# Tastendruckverlaengerer_1_3a.net
KiCad netlist of a schematic drawn in EAGLE
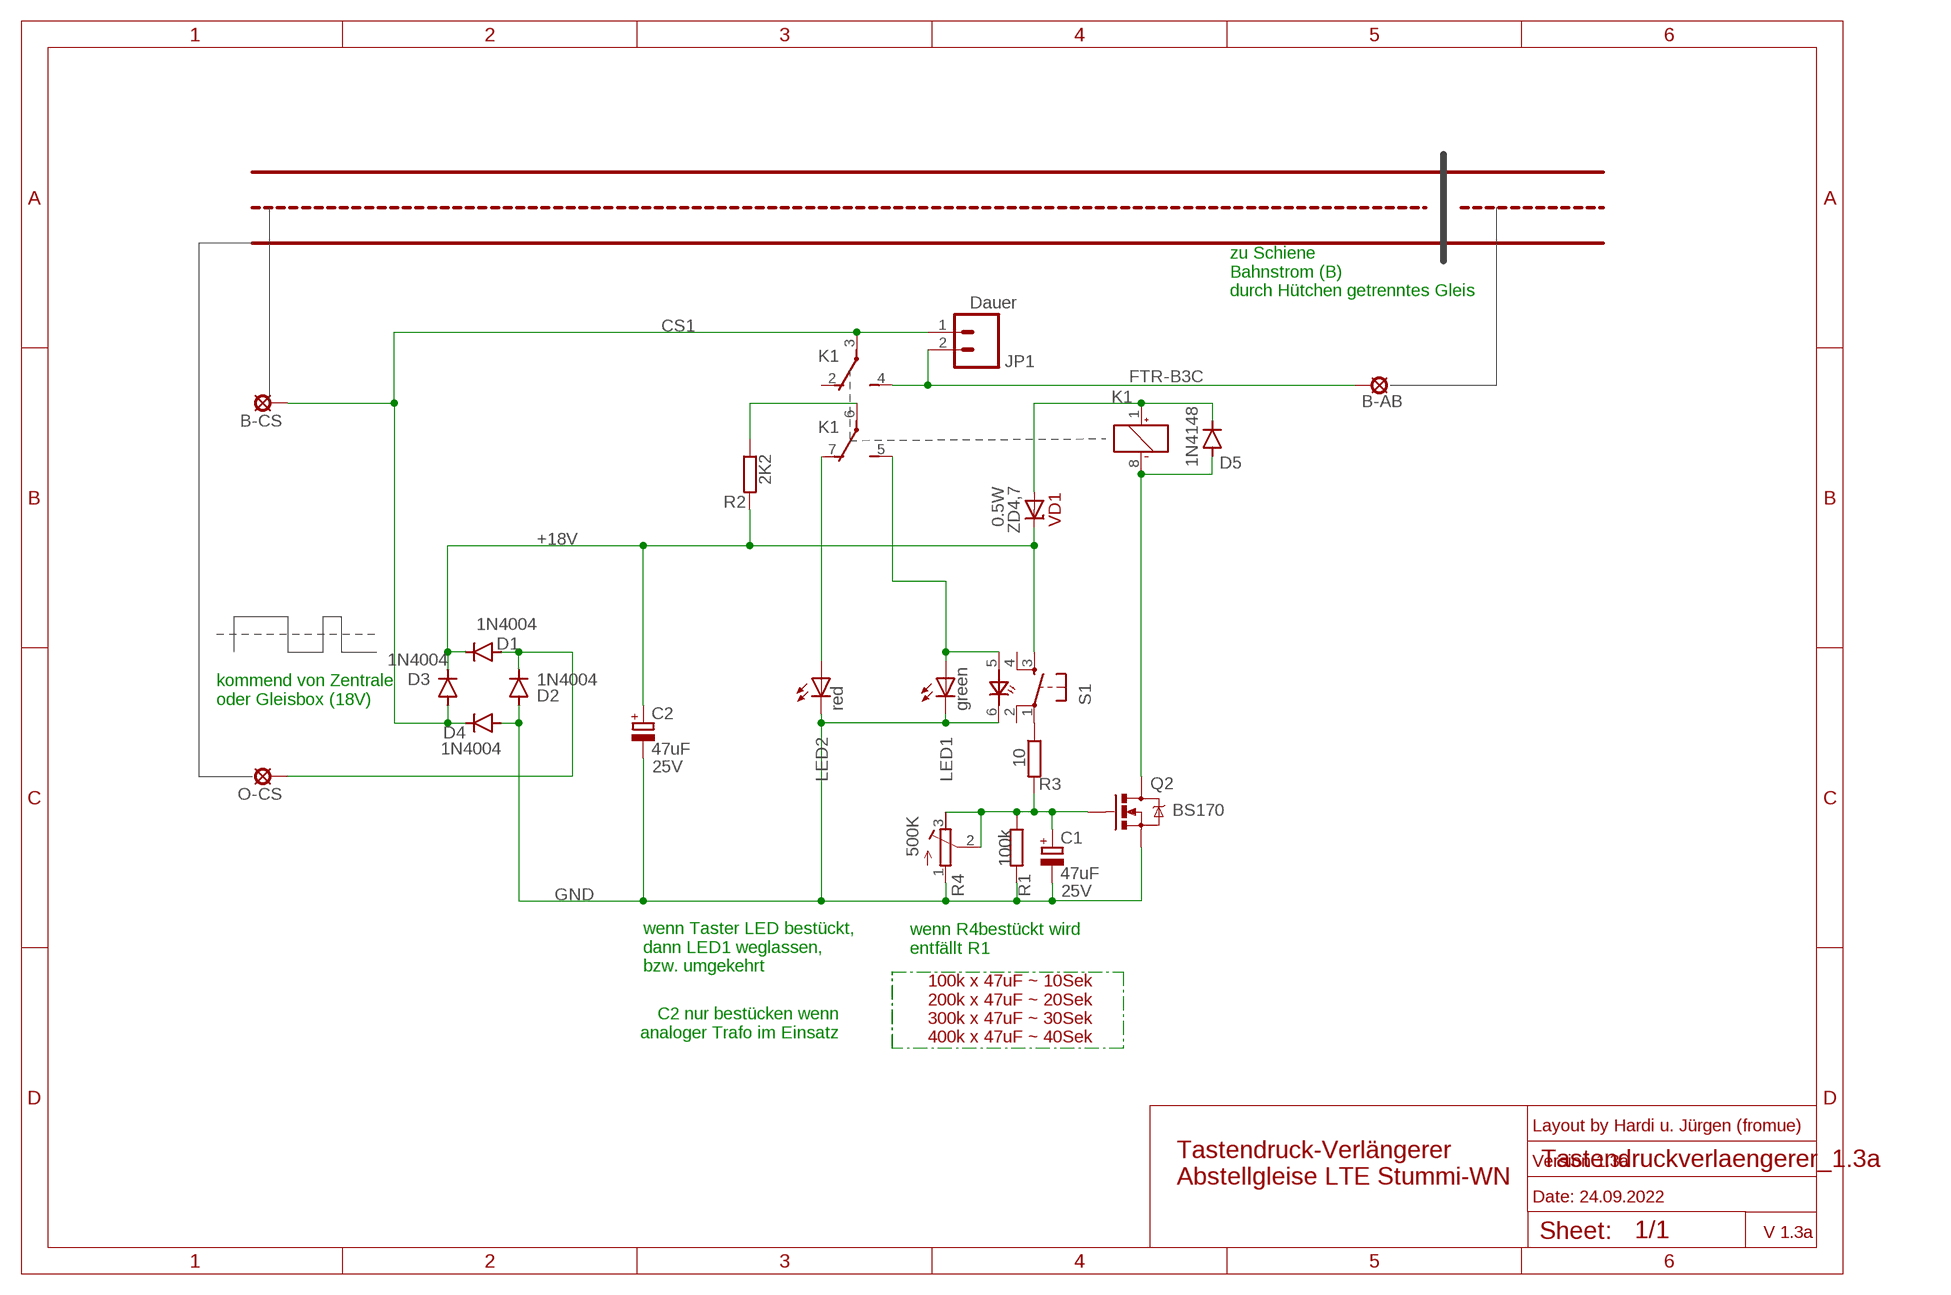
[diagram p0: schematic, sheet 1]

(export (version "E")
  (design (tool "Eeschema 10.0.6"))
  (components
    (comp (ref "B-AB")
      (value "SE14")
      (footprint "eagle-import:SE14")
      (libsource (lib "eagle-import") (part "SE14"))
    )
    (comp (ref "B-CS")
      (value "SE14")
      (footprint "eagle-import:SE14")
      (libsource (lib "eagle-import") (part "SE14"))
    )
    (comp (ref "C1")
      (value "47uF")
      (footprint "eagle-import:TT2D5L")
      (fields (field (name "ADD") "25V"))
      (libsource (lib "eagle-import") (part "CPOL-EUTT2D5L"))
    )
    (comp (ref "C2")
      (value "47uF")
      (footprint "eagle-import:TT2D5L")
      (fields (field (name "ADD") "25V"))
      (libsource (lib "eagle-import") (part "CPOL-EUTT2D5L"))
    )
    (comp (ref "D1")
      (value "1N4004")
      (footprint "eagle-import:DO41-10A")
      (libsource (lib "eagle-import") (part "1N4004DO41-10A"))
    )
    (comp (ref "D2")
      (value "1N4004")
      (footprint "eagle-import:DO41-10A")
      (libsource (lib "eagle-import") (part "1N4004DO41-10A"))
    )
    (comp (ref "D3")
      (value "1N4004")
      (footprint "eagle-import:DO41-10A")
      (libsource (lib "eagle-import") (part "1N4004DO41-10A"))
    )
    (comp (ref "D4")
      (value "1N4004")
      (footprint "eagle-import:DO41-10A")
      (libsource (lib "eagle-import") (part "1N4004DO41-10A"))
    )
    (comp (ref "D5")
      (value "1N4148")
      (footprint "eagle-import:DO35-7")
      (fields (field (name "SPICEPREFIX") "D"))
      (libsource (lib "eagle-import") (part "1N4148DO35-7"))
    )
    (comp (ref "JP1")
      (value "Dauer")
      (footprint "eagle-import:1X02")
      (libsource (lib "eagle-import") (part "M02PTH"))
    )
    (comp (ref "K1")
      (value "FTR-B3C")
      (footprint "eagle-import:FTR-B4C")
      (libsource (lib "eagle-import") (part "FTR-B3C"))
    )
    (comp (ref "LED1")
      (value "green")
      (footprint "eagle-import:LED3MM")
      (libsource (lib "eagle-import") (part "LED3MM"))
    )
    (comp (ref "LED2")
      (value "red")
      (footprint "eagle-import:LED3MM")
      (libsource (lib "eagle-import") (part "LED3MM"))
    )
    (comp (ref "O-CS")
      (value "SE14")
      (footprint "eagle-import:SE14")
      (libsource (lib "eagle-import") (part "SE14"))
    )
    (comp (ref "Q2")
      (value "BS170")
      (footprint "eagle-import:TO-92")
      (libsource (lib "eagle-import") (part "MOSFET-NCHANNELBS170"))
    )
    (comp (ref "R1")
      (value "100k")
      (footprint "eagle-import:0204_7")
      (libsource (lib "eagle-import") (part "R0204/7"))
    )
    (comp (ref "R2")
      (value "2K2")
      (footprint "eagle-import:0204_7")
      (fields (field (name "SPICEPREFIX") "4k7"))
      (libsource (lib "eagle-import") (part "R0204/7"))
    )
    (comp (ref "R3")
      (value "10")
      (footprint "eagle-import:0204_7")
      (libsource (lib "eagle-import") (part "R0204/7"))
    )
    (comp (ref "R4")
      (value "500K")
      (footprint "eagle-import:RTRIM3296W")
      (libsource (lib "eagle-import") (part "R-TRIMM3296W"))
    )
    (comp (ref "S1")
      (value "TASTER_LEDTC-1198-B")
      (footprint "eagle-import:TASTER_LED")
      (libsource (lib "eagle-import") (part "TASTER_LEDTC-1198-B"))
    )
    (comp (ref "VD1")
      (value "ZD4,7")
      (footprint "eagle-import:DIODES-ZENER_DO35-7")
      (fields (field (name "MOUSER") "ZF4.7") (field (name "POWER") "0.5W"))
      (libsource (lib "eagle-import") (part "DIODES-ZENER_?5.6V(1N5232)"))
    )
  )
  (nets
    (net (code "1") (name "/+18V") (class "Default")
      (node (ref "C2") (pin "+") (pinfunction "+_+") (pintype "passive"))
      (node (ref "D1") (pin "C") (pinfunction "C_C") (pintype "passive"))
      (node (ref "D3") (pin "C") (pinfunction "C_C") (pintype "passive"))
      (node (ref "R2") (pin "2") (pinfunction "2_2") (pintype "passive"))
      (node (ref "S1") (pin "3") (pinfunction "S_3") (pintype "passive"))
      (node (ref "VD1") (pin "C") (pinfunction "C_C") (pintype "passive"))
    )
    (net (code "2") (name "/CS1") (class "Default")
      (node (ref "B-CS") (pin "MP") (pinfunction "MP_MP") (pintype "passive"))
      (node (ref "D3") (pin "A") (pinfunction "A_A") (pintype "passive"))
      (node (ref "D4") (pin "C") (pinfunction "C_C") (pintype "passive"))
      (node (ref "JP1") (pin "1") (pinfunction "1_1") (pintype "passive"))
      (node (ref "K1") (pin "3") (pinfunction "P_3") (pintype "passive"))
    )
    (net (code "3") (name "/GND") (class "Default")
      (node (ref "C1") (pin "-") (pinfunction "-_-") (pintype "passive"))
      (node (ref "C2") (pin "-") (pinfunction "-_-") (pintype "passive"))
      (node (ref "D2") (pin "A") (pinfunction "A_A") (pintype "passive"))
      (node (ref "D4") (pin "A") (pinfunction "A_A") (pintype "passive"))
      (node (ref "LED1") (pin "K") (pinfunction "C_K") (pintype "passive"))
      (node (ref "LED2") (pin "K") (pinfunction "C_K") (pintype "passive"))
      (node (ref "Q2") (pin "3") (pinfunction "S_3") (pintype "passive"))
      (node (ref "R1") (pin "2") (pinfunction "2_2") (pintype "passive"))
      (node (ref "R4") (pin "1") (pinfunction "A_1") (pintype "passive"))
      (node (ref "S1") (pin "6") (pinfunction "-_6") (pintype "input"))
    )
    (net (code "4") (name "Net-(D1-PadA)") (class "Default")
      (node (ref "D1") (pin "A") (pinfunction "A_A") (pintype "passive"))
      (node (ref "D2") (pin "C") (pinfunction "C_C") (pintype "passive"))
      (node (ref "O-CS") (pin "MP") (pinfunction "MP_MP") (pintype "passive"))
    )
    (net (code "5") (name "Net-(K1A-S)") (class "Default")
      (node (ref "B-AB") (pin "MP") (pinfunction "MP_MP") (pintype "passive"))
      (node (ref "JP1") (pin "2") (pinfunction "2_2") (pintype "passive"))
      (node (ref "K1") (pin "4") (pinfunction "S_4") (pintype "passive"))
    )
    (net (code "6") (name "Net-(K1B-O)") (class "Default")
      (node (ref "K1") (pin "7") (pinfunction "O_7") (pintype "passive"))
      (node (ref "LED2") (pin "A") (pinfunction "A_A") (pintype "passive"))
    )
    (net (code "7") (name "Net-(K1B-P)") (class "Default")
      (node (ref "K1") (pin "6") (pinfunction "P_6") (pintype "passive"))
      (node (ref "R2") (pin "1") (pinfunction "1_1") (pintype "passive"))
    )
    (net (code "8") (name "Net-(K1B-S)") (class "Default")
      (node (ref "K1") (pin "5") (pinfunction "S_5") (pintype "passive"))
      (node (ref "LED1") (pin "A") (pinfunction "A_A") (pintype "passive"))
      (node (ref "S1") (pin "5") (pinfunction "+_5") (pintype "input"))
    )
    (net (code "9") (name "Net-(K1C-+)") (class "Default")
      (node (ref "D5") (pin "C") (pinfunction "C_C") (pintype "passive"))
      (node (ref "K1") (pin "1") (pinfunction "+_1") (pintype "passive"))
      (node (ref "VD1") (pin "A") (pinfunction "A_A") (pintype "passive"))
    )
    (net (code "10") (name "Net-(K1C--)") (class "Default")
      (node (ref "D5") (pin "A") (pinfunction "A_A") (pintype "passive"))
      (node (ref "K1") (pin "8") (pinfunction "-_8") (pintype "passive"))
      (node (ref "Q2") (pin "1") (pinfunction "D_1") (pintype "passive"))
    )
    (net (code "11") (name "Net-(Q2-G)") (class "Default")
      (node (ref "C1") (pin "+") (pinfunction "+_+") (pintype "passive"))
      (node (ref "Q2") (pin "2") (pinfunction "G_2") (pintype "passive"))
      (node (ref "R1") (pin "1") (pinfunction "1_1") (pintype "passive"))
      (node (ref "R3") (pin "2") (pinfunction "2_2") (pintype "passive"))
      (node (ref "R4") (pin "2") (pinfunction "S_2") (pintype "passive"))
      (node (ref "R4") (pin "3") (pinfunction "E_3") (pintype "passive"))
    )
    (net (code "12") (name "Net-(S1-P)") (class "Default")
      (node (ref "R3") (pin "1") (pinfunction "1_1") (pintype "passive"))
      (node (ref "S1") (pin "1") (pinfunction "P_1") (pintype "passive"))
    )
    (net (code "13") (name "unconnected-(K1A-O-Pad2)") (class "Default")
      (node (ref "K1") (pin "2") (pinfunction "O_2") (pintype "passive"))
    )
    (net (code "14") (name "unconnected-(S1-P1-Pad2)") (class "Default")
      (node (ref "S1") (pin "2") (pinfunction "P1_2") (pintype "passive"))
    )
    (net (code "15") (name "unconnected-(S1-S1-Pad4)") (class "Default")
      (node (ref "S1") (pin "4") (pinfunction "S1_4") (pintype "passive"))
    )
  )
)
